# LED_Thermo.net
KiCad netlist of a schematic drawn in EAGLE
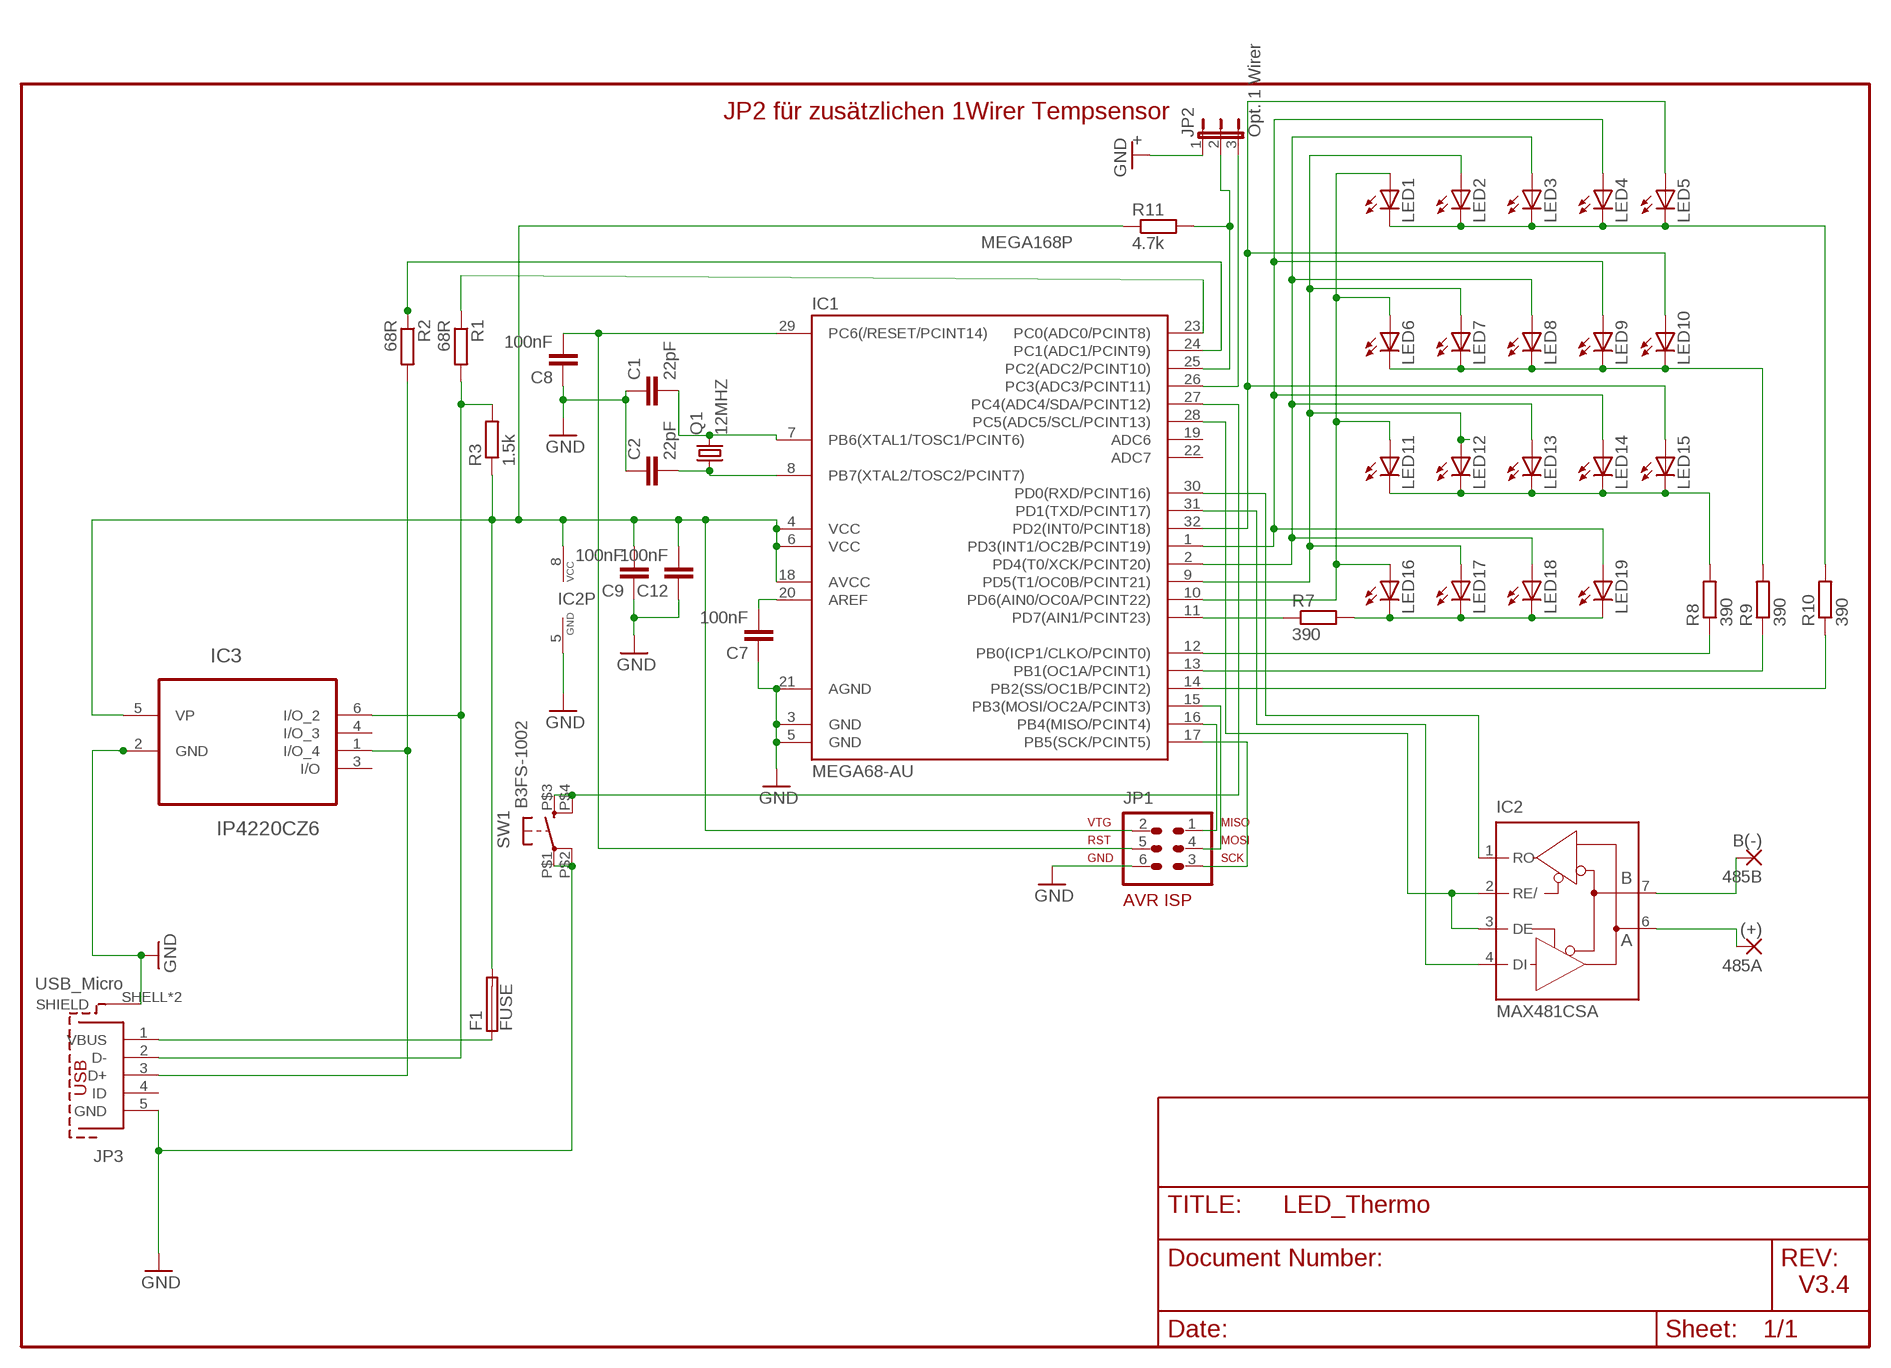
[diagram p0: schematic, sheet 1]

(export (version "E")
  (design (tool "Eeschema 10.0.6"))
  (components
    (comp (ref "485A")
      (value "(+)")
      (footprint "eagle-import:2,54_1,0")
      (libsource (lib "eagle-import") (part "2,54/1,0"))
    )
    (comp (ref "485B")
      (value "B(-)")
      (footprint "eagle-import:2,54_1,0")
      (libsource (lib "eagle-import") (part "2,54/1,0"))
    )
    (comp (ref "C1")
      (value "22pF")
      (footprint "eagle-import:C0805")
      (libsource (lib "eagle-import") (part "C-EUC0805"))
    )
    (comp (ref "C2")
      (value "22pF")
      (footprint "eagle-import:C0805")
      (libsource (lib "eagle-import") (part "C-EUC0805"))
    )
    (comp (ref "C7")
      (value "100nF")
      (footprint "eagle-import:C0805")
      (libsource (lib "eagle-import") (part "C-EUC0805"))
    )
    (comp (ref "C8")
      (value "100nF")
      (footprint "eagle-import:C0805")
      (libsource (lib "eagle-import") (part "C-EUC0805"))
    )
    (comp (ref "C9")
      (value "100nF")
      (footprint "eagle-import:C0805")
      (libsource (lib "eagle-import") (part "C-EUC0805"))
    )
    (comp (ref "C12")
      (value "100nF")
      (footprint "eagle-import:C0805")
      (libsource (lib "eagle-import") (part "C-EUC0805"))
    )
    (comp (ref "F1")
      (value "FUSE")
      (footprint "eagle-import:FUSE_1206")
      (libsource (lib "eagle-import") (part "FUSE"))
    )
    (comp (ref "IC1")
      (value "MEGA68-AU")
      (footprint "eagle-import:TQFP32-08")
      (libsource (lib "eagle-import") (part "MEGA48/88/168-AU"))
    )
    (comp (ref "IC2")
      (value "MAX481CSA")
      (footprint "eagle-import:SO08")
      (libsource (lib "eagle-import") (part "MAX481CSA"))
    )
    (comp (ref "IC3")
      (value "IP4220CZ6")
      (footprint "eagle-import:SOT95P275X110-6N")
      (fields (field (name "MF") "Nexperia USA"))
      (libsource (lib "eagle-import") (part "IP4220CZ6"))
    )
    (comp (ref "JP1")
      (value "AVR-ISP-6")
      (footprint "eagle-import:AVR-ISP-6")
      (libsource (lib "eagle-import") (part "AVR-ISP-6"))
    )
    (comp (ref "JP2")
      (value "Opt. 1 Wirer")
      (footprint "eagle-import:JP2")
      (libsource (lib "eagle-import") (part "JP2E"))
    )
    (comp (ref "JP3")
      (value "USB_Micro")
      (footprint "eagle-import:614105150721")
      (libsource (lib "eagle-import") (part "614105150721"))
    )
    (comp (ref "LED1")
      (value "LED3MM")
      (footprint "eagle-import:LED3MM")
      (libsource (lib "eagle-import") (part "LED3MM"))
    )
    (comp (ref "LED2")
      (value "LED3MM")
      (footprint "eagle-import:LED3MM")
      (libsource (lib "eagle-import") (part "LED3MM"))
    )
    (comp (ref "LED3")
      (value "LED3MM")
      (footprint "eagle-import:LED3MM")
      (libsource (lib "eagle-import") (part "LED3MM"))
    )
    (comp (ref "LED4")
      (value "LED3MM")
      (footprint "eagle-import:LED3MM")
      (libsource (lib "eagle-import") (part "LED3MM"))
    )
    (comp (ref "LED5")
      (value "LED3MM")
      (footprint "eagle-import:LED3MM")
      (libsource (lib "eagle-import") (part "LED3MM"))
    )
    (comp (ref "LED6")
      (value "LED3MM")
      (footprint "eagle-import:LED3MM")
      (libsource (lib "eagle-import") (part "LED3MM"))
    )
    (comp (ref "LED7")
      (value "LED3MM")
      (footprint "eagle-import:LED3MM")
      (libsource (lib "eagle-import") (part "LED3MM"))
    )
    (comp (ref "LED8")
      (value "LED3MM")
      (footprint "eagle-import:LED3MM")
      (libsource (lib "eagle-import") (part "LED3MM"))
    )
    (comp (ref "LED9")
      (value "LED3MM")
      (footprint "eagle-import:LED3MM")
      (libsource (lib "eagle-import") (part "LED3MM"))
    )
    (comp (ref "LED10")
      (value "LED3MM")
      (footprint "eagle-import:LED3MM")
      (libsource (lib "eagle-import") (part "LED3MM"))
    )
    (comp (ref "LED11")
      (value "LED3MM")
      (footprint "eagle-import:LED3MM")
      (libsource (lib "eagle-import") (part "LED3MM"))
    )
    (comp (ref "LED12")
      (value "LED3MM")
      (footprint "eagle-import:LED3MM")
      (libsource (lib "eagle-import") (part "LED3MM"))
    )
    (comp (ref "LED13")
      (value "LED3MM")
      (footprint "eagle-import:LED3MM")
      (libsource (lib "eagle-import") (part "LED3MM"))
    )
    (comp (ref "LED14")
      (value "LED3MM")
      (footprint "eagle-import:LED3MM")
      (libsource (lib "eagle-import") (part "LED3MM"))
    )
    (comp (ref "LED15")
      (value "LED3MM")
      (footprint "eagle-import:LED3MM")
      (libsource (lib "eagle-import") (part "LED3MM"))
    )
    (comp (ref "LED16")
      (value "LED3MM")
      (footprint "eagle-import:LED3MM")
      (libsource (lib "eagle-import") (part "LED3MM"))
    )
    (comp (ref "LED17")
      (value "LED3MM")
      (footprint "eagle-import:LED3MM")
      (libsource (lib "eagle-import") (part "LED3MM"))
    )
    (comp (ref "LED18")
      (value "LED3MM")
      (footprint "eagle-import:LED3MM")
      (libsource (lib "eagle-import") (part "LED3MM"))
    )
    (comp (ref "LED19")
      (value "LED3MM")
      (footprint "eagle-import:LED3MM")
      (libsource (lib "eagle-import") (part "LED3MM"))
    )
    (comp (ref "Q1")
      (value "12MHZ")
      (footprint "eagle-import:HC18U-V")
      (libsource (lib "eagle-import") (part "CRYSTALHC18U-V"))
    )
    (comp (ref "R1")
      (value "68R")
      (footprint "eagle-import:M0805")
      (libsource (lib "eagle-import") (part "R-EU_M0805"))
    )
    (comp (ref "R2")
      (value "68R")
      (footprint "eagle-import:M0805")
      (libsource (lib "eagle-import") (part "R-EU_M0805"))
    )
    (comp (ref "R3")
      (value "1.5k")
      (footprint "eagle-import:M0805")
      (libsource (lib "eagle-import") (part "R-EU_M0805"))
    )
    (comp (ref "R7")
      (value "390")
      (footprint "eagle-import:M0805")
      (libsource (lib "eagle-import") (part "R-EU_M0805"))
    )
    (comp (ref "R8")
      (value "390")
      (footprint "eagle-import:M0805")
      (libsource (lib "eagle-import") (part "R-EU_M0805"))
    )
    (comp (ref "R9")
      (value "390")
      (footprint "eagle-import:M0805")
      (libsource (lib "eagle-import") (part "R-EU_M0805"))
    )
    (comp (ref "R10")
      (value "390")
      (footprint "eagle-import:M0805")
      (libsource (lib "eagle-import") (part "R-EU_M0805"))
    )
    (comp (ref "R11")
      (value "4.7k")
      (footprint "eagle-import:M0805")
      (libsource (lib "eagle-import") (part "R-EU_M0805"))
    )
    (comp (ref "SW1")
      (value "B3FS-1002")
      (footprint "eagle-import:B3FS-1002")
      (libsource (lib "eagle-import") (part "B3FS-10XX"))
    )
  )
  (nets
    (net (code "1") (name "GND") (class "Default")
      (node (ref "C1") (pin "1") (pinfunction "1_1") (pintype "passive"))
      (node (ref "C12") (pin "1") (pinfunction "1_1") (pintype "passive"))
      (node (ref "C2") (pin "1") (pinfunction "1_1") (pintype "passive"))
      (node (ref "C7") (pin "1") (pinfunction "1_1") (pintype "passive"))
      (node (ref "C8") (pin "1") (pinfunction "1_1") (pintype "passive"))
      (node (ref "C9") (pin "1") (pinfunction "1_1") (pintype "passive"))
      (node (ref "IC1") (pin "21") (pinfunction "AGND_21") (pintype "power_in"))
      (node (ref "IC1") (pin "3") (pinfunction "GND_3") (pintype "power_in"))
      (node (ref "IC1") (pin "5") (pinfunction "GND_5") (pintype "power_in"))
      (node (ref "IC2") (pin "5") (pinfunction "GND_5") (pintype "power_in"))
      (node (ref "IC3") (pin "2") (pinfunction "GND_2") (pintype "passive"))
      (node (ref "JP1") (pin "6") (pinfunction "6_6") (pintype "passive"))
      (node (ref "JP2") (pin "1") (pinfunction "1_1") (pintype "passive"))
      (node (ref "JP3") (pin "5") (pinfunction "GND_5") (pintype "passive"))
      (node (ref "JP3") (pin "SHELL") (pinfunction "SHIELD_SHELL") (pintype "passive"))
      (node (ref "JP3") (pin "SHELL1") (pinfunction "SHIELD_SHELL1") (pintype "passive"))
      (node (ref "SW1") (pin "P$1") (pinfunction "P_P$1") (pintype "passive"))
      (node (ref "SW1") (pin "P$2") (pinfunction "P1_P$2") (pintype "passive"))
    )
    (net (code "2") (name "Net-(485A-P)") (class "Default")
      (node (ref "485A") (pin "1") (pinfunction "P_1") (pintype "passive"))
      (node (ref "IC2") (pin "6") (pinfunction "A_6") (pintype "passive"))
    )
    (net (code "3") (name "Net-(485B-P)") (class "Default")
      (node (ref "485B") (pin "1") (pinfunction "P_1") (pintype "passive"))
      (node (ref "IC2") (pin "7") (pinfunction "B_7") (pintype "passive"))
    )
    (net (code "4") (name "Net-(IC1-AREF)") (class "Default")
      (node (ref "C7") (pin "2") (pinfunction "2_2") (pintype "passive"))
      (node (ref "IC1") (pin "20") (pinfunction "AREF_20") (pintype "passive"))
    )
    (net (code "5") (name "Net-(IC1-AVCC)") (class "Default")
      (node (ref "C12") (pin "2") (pinfunction "2_2") (pintype "passive"))
      (node (ref "C9") (pin "2") (pinfunction "2_2") (pintype "passive"))
      (node (ref "F1") (pin "2") (pinfunction "2_2") (pintype "passive"))
      (node (ref "IC1") (pin "18") (pinfunction "AVCC_18") (pintype "passive"))
      (node (ref "IC1") (pin "4") (pinfunction "VCC_4") (pintype "power_in"))
      (node (ref "IC1") (pin "6") (pinfunction "VCC_6") (pintype "power_in"))
      (node (ref "IC2") (pin "8") (pinfunction "VCC_8") (pintype "power_in"))
      (node (ref "IC3") (pin "5") (pinfunction "VP_5") (pintype "power_in"))
      (node (ref "JP1") (pin "2") (pinfunction "2_2") (pintype "passive"))
      (node (ref "R11") (pin "1") (pinfunction "1_1") (pintype "passive"))
      (node (ref "R3") (pin "1") (pinfunction "1_1") (pintype "passive"))
    )
    (net (code "6") (name "Net-(IC1-PB0(ICP1{slash}CLKO{slash}PCINT0))") (class "Default")
      (node (ref "IC1") (pin "12") (pinfunction "PB0(ICP1/CLKO/PCINT0)_12") (pintype "bidirectional"))
      (node (ref "R8") (pin "1") (pinfunction "1_1") (pintype "passive"))
    )
    (net (code "7") (name "Net-(IC1-PB1(OC1A{slash}PCINT1))") (class "Default")
      (node (ref "IC1") (pin "13") (pinfunction "PB1(OC1A/PCINT1)_13") (pintype "bidirectional"))
      (node (ref "R9") (pin "1") (pinfunction "1_1") (pintype "passive"))
    )
    (net (code "8") (name "Net-(IC1-PB2(SS{slash}OC1B{slash}PCINT2))") (class "Default")
      (node (ref "IC1") (pin "14") (pinfunction "PB2(SS/OC1B/PCINT2)_14") (pintype "bidirectional"))
      (node (ref "R10") (pin "1") (pinfunction "1_1") (pintype "passive"))
    )
    (net (code "9") (name "Net-(IC1-PB3(MOSI{slash}OC2A{slash}PCINT3))") (class "Default")
      (node (ref "IC1") (pin "15") (pinfunction "PB3(MOSI/OC2A/PCINT3)_15") (pintype "bidirectional"))
      (node (ref "JP1") (pin "4") (pinfunction "4_4") (pintype "passive"))
    )
    (net (code "10") (name "Net-(IC1-PB4(MISO{slash}PCINT4))") (class "Default")
      (node (ref "IC1") (pin "16") (pinfunction "PB4(MISO/PCINT4)_16") (pintype "bidirectional"))
      (node (ref "JP1") (pin "1") (pinfunction "1_1") (pintype "passive"))
    )
    (net (code "11") (name "Net-(IC1-PB5(SCK{slash}PCINT5))") (class "Default")
      (node (ref "IC1") (pin "17") (pinfunction "PB5(SCK/PCINT5)_17") (pintype "bidirectional"))
      (node (ref "JP1") (pin "3") (pinfunction "3_3") (pintype "passive"))
    )
    (net (code "12") (name "Net-(IC1-PB6(XTAL1{slash}TOSC1{slash}PCINT6))") (class "Default")
      (node (ref "C1") (pin "2") (pinfunction "2_2") (pintype "passive"))
      (node (ref "IC1") (pin "7") (pinfunction "PB6(XTAL1/TOSC1/PCINT6)_7") (pintype "bidirectional"))
      (node (ref "Q1") (pin "2") (pinfunction "2_2") (pintype "passive"))
    )
    (net (code "13") (name "Net-(IC1-PB7(XTAL2{slash}TOSC2{slash}PCINT7))") (class "Default")
      (node (ref "C2") (pin "2") (pinfunction "2_2") (pintype "passive"))
      (node (ref "IC1") (pin "8") (pinfunction "PB7(XTAL2/TOSC2/PCINT7)_8") (pintype "bidirectional"))
      (node (ref "Q1") (pin "1") (pinfunction "1_1") (pintype "passive"))
    )
    (net (code "14") (name "Net-(IC1-PC0(ADC0{slash}PCINT8))") (class "Default")
      (node (ref "IC1") (pin "23") (pinfunction "PC0(ADC0/PCINT8)_23") (pintype "bidirectional"))
      (node (ref "R1") (pin "1") (pinfunction "1_1") (pintype "passive"))
    )
    (net (code "15") (name "Net-(IC1-PC1(ADC1{slash}PCINT9))") (class "Default")
      (node (ref "IC1") (pin "24") (pinfunction "PC1(ADC1/PCINT9)_24") (pintype "bidirectional"))
      (node (ref "R2") (pin "1") (pinfunction "1_1") (pintype "passive"))
    )
    (net (code "16") (name "Net-(IC1-PC2(ADC2{slash}PCINT10))") (class "Default")
      (node (ref "IC1") (pin "25") (pinfunction "PC2(ADC2/PCINT10)_25") (pintype "bidirectional"))
      (node (ref "JP2") (pin "2") (pinfunction "2_2") (pintype "passive"))
      (node (ref "R11") (pin "2") (pinfunction "2_2") (pintype "passive"))
    )
    (net (code "17") (name "Net-(IC1-PC3(ADC3{slash}PCINT11))") (class "Default")
      (node (ref "IC1") (pin "26") (pinfunction "PC3(ADC3/PCINT11)_26") (pintype "bidirectional"))
      (node (ref "JP2") (pin "3") (pinfunction "3_3") (pintype "passive"))
    )
    (net (code "18") (name "Net-(IC1-PC4(ADC4{slash}SDA{slash}PCINT12))") (class "Default")
      (node (ref "IC1") (pin "27") (pinfunction "PC4(ADC4/SDA/PCINT12)_27") (pintype "bidirectional"))
      (node (ref "SW1") (pin "P$3") (pinfunction "S_P$3") (pintype "passive"))
      (node (ref "SW1") (pin "P$4") (pinfunction "S1_P$4") (pintype "passive"))
    )
    (net (code "19") (name "Net-(IC1-PC5(ADC5{slash}SCL{slash}PCINT13))") (class "Default")
      (node (ref "IC1") (pin "28") (pinfunction "PC5(ADC5/SCL/PCINT13)_28") (pintype "bidirectional"))
      (node (ref "IC2") (pin "2") (pinfunction "RE/_2") (pintype "input"))
      (node (ref "IC2") (pin "3") (pinfunction "DE_3") (pintype "input"))
    )
    (net (code "20") (name "Net-(IC1-PC6({slash}RESET{slash}PCINT14))") (class "Default")
      (node (ref "C8") (pin "2") (pinfunction "2_2") (pintype "passive"))
      (node (ref "IC1") (pin "29") (pinfunction "PC6(/RESET/PCINT14)_29") (pintype "bidirectional"))
      (node (ref "JP1") (pin "5") (pinfunction "5_5") (pintype "passive"))
    )
    (net (code "21") (name "Net-(IC1-PD0(RXD{slash}PCINT16))") (class "Default")
      (node (ref "IC1") (pin "30") (pinfunction "PD0(RXD/PCINT16)_30") (pintype "bidirectional"))
      (node (ref "IC2") (pin "1") (pinfunction "RO_1") (pintype "output"))
    )
    (net (code "22") (name "Net-(IC1-PD1(TXD{slash}PCINT17))") (class "Default")
      (node (ref "IC1") (pin "31") (pinfunction "PD1(TXD/PCINT17)_31") (pintype "bidirectional"))
      (node (ref "IC2") (pin "4") (pinfunction "DI_4") (pintype "input"))
    )
    (net (code "23") (name "Net-(IC1-PD2(INT0{slash}PCINT18))") (class "Default")
      (node (ref "IC1") (pin "32") (pinfunction "PD2(INT0/PCINT18)_32") (pintype "bidirectional"))
      (node (ref "LED10") (pin "A") (pinfunction "A_A") (pintype "passive"))
      (node (ref "LED15") (pin "A") (pinfunction "A_A") (pintype "passive"))
      (node (ref "LED5") (pin "A") (pinfunction "A_A") (pintype "passive"))
    )
    (net (code "24") (name "Net-(IC1-PD3(INT1{slash}OC2B{slash}PCINT19))") (class "Default")
      (node (ref "IC1") (pin "1") (pinfunction "PD3(INT1/OC2B/PCINT19)_1") (pintype "bidirectional"))
      (node (ref "LED14") (pin "A") (pinfunction "A_A") (pintype "passive"))
      (node (ref "LED19") (pin "A") (pinfunction "A_A") (pintype "passive"))
      (node (ref "LED4") (pin "A") (pinfunction "A_A") (pintype "passive"))
      (node (ref "LED9") (pin "A") (pinfunction "A_A") (pintype "passive"))
    )
    (net (code "25") (name "Net-(IC1-PD4(T0{slash}XCK{slash}PCINT20))") (class "Default")
      (node (ref "IC1") (pin "2") (pinfunction "PD4(T0/XCK/PCINT20)_2") (pintype "bidirectional"))
      (node (ref "LED13") (pin "A") (pinfunction "A_A") (pintype "passive"))
      (node (ref "LED18") (pin "A") (pinfunction "A_A") (pintype "passive"))
      (node (ref "LED3") (pin "A") (pinfunction "A_A") (pintype "passive"))
      (node (ref "LED8") (pin "A") (pinfunction "A_A") (pintype "passive"))
    )
    (net (code "26") (name "Net-(IC1-PD5(T1{slash}OC0B{slash}PCINT21))") (class "Default")
      (node (ref "IC1") (pin "9") (pinfunction "PD5(T1/OC0B/PCINT21)_9") (pintype "bidirectional"))
      (node (ref "LED12") (pin "A") (pinfunction "A_A") (pintype "passive"))
      (node (ref "LED17") (pin "A") (pinfunction "A_A") (pintype "passive"))
      (node (ref "LED2") (pin "A") (pinfunction "A_A") (pintype "passive"))
      (node (ref "LED7") (pin "A") (pinfunction "A_A") (pintype "passive"))
    )
    (net (code "27") (name "Net-(IC1-PD6(AIN0{slash}OC0A{slash}PCINT22))") (class "Default")
      (node (ref "IC1") (pin "10") (pinfunction "PD6(AIN0/OC0A/PCINT22)_10") (pintype "bidirectional"))
      (node (ref "LED1") (pin "A") (pinfunction "A_A") (pintype "passive"))
      (node (ref "LED11") (pin "A") (pinfunction "A_A") (pintype "passive"))
      (node (ref "LED16") (pin "A") (pinfunction "A_A") (pintype "passive"))
      (node (ref "LED6") (pin "A") (pinfunction "A_A") (pintype "passive"))
    )
    (net (code "28") (name "Net-(IC1-PD7(AIN1{slash}PCINT23))") (class "Default")
      (node (ref "IC1") (pin "11") (pinfunction "PD7(AIN1/PCINT23)_11") (pintype "bidirectional"))
      (node (ref "R7") (pin "1") (pinfunction "1_1") (pintype "passive"))
    )
    (net (code "29") (name "Net-(IC3-I{slash}O_2)") (class "Default")
      (node (ref "IC3") (pin "6") (pinfunction "I/O_2_6") (pintype "bidirectional"))
      (node (ref "JP3") (pin "2") (pinfunction "D-_2") (pintype "passive"))
      (node (ref "R1") (pin "2") (pinfunction "2_2") (pintype "passive"))
      (node (ref "R3") (pin "2") (pinfunction "2_2") (pintype "passive"))
    )
    (net (code "30") (name "Net-(IC3-I{slash}O_4)") (class "Default")
      (node (ref "IC3") (pin "1") (pinfunction "I/O_4_1") (pintype "bidirectional"))
      (node (ref "JP3") (pin "3") (pinfunction "D+_3") (pintype "passive"))
      (node (ref "R2") (pin "2") (pinfunction "2_2") (pintype "passive"))
    )
    (net (code "31") (name "Net-(JP3-VBUS)") (class "Default")
      (node (ref "F1") (pin "1") (pinfunction "1_1") (pintype "passive"))
      (node (ref "JP3") (pin "1") (pinfunction "VBUS_1") (pintype "passive"))
    )
    (net (code "32") (name "Net-(LED1-C)") (class "Default")
      (node (ref "LED1") (pin "K") (pinfunction "C_K") (pintype "passive"))
      (node (ref "LED2") (pin "K") (pinfunction "C_K") (pintype "passive"))
      (node (ref "LED3") (pin "K") (pinfunction "C_K") (pintype "passive"))
      (node (ref "LED4") (pin "K") (pinfunction "C_K") (pintype "passive"))
      (node (ref "LED5") (pin "K") (pinfunction "C_K") (pintype "passive"))
      (node (ref "R10") (pin "2") (pinfunction "2_2") (pintype "passive"))
    )
    (net (code "33") (name "Net-(LED10-C)") (class "Default")
      (node (ref "LED10") (pin "K") (pinfunction "C_K") (pintype "passive"))
      (node (ref "LED6") (pin "K") (pinfunction "C_K") (pintype "passive"))
      (node (ref "LED7") (pin "K") (pinfunction "C_K") (pintype "passive"))
      (node (ref "LED8") (pin "K") (pinfunction "C_K") (pintype "passive"))
      (node (ref "LED9") (pin "K") (pinfunction "C_K") (pintype "passive"))
      (node (ref "R9") (pin "2") (pinfunction "2_2") (pintype "passive"))
    )
    (net (code "34") (name "Net-(LED11-C)") (class "Default")
      (node (ref "LED11") (pin "K") (pinfunction "C_K") (pintype "passive"))
      (node (ref "LED12") (pin "K") (pinfunction "C_K") (pintype "passive"))
      (node (ref "LED13") (pin "K") (pinfunction "C_K") (pintype "passive"))
      (node (ref "LED14") (pin "K") (pinfunction "C_K") (pintype "passive"))
      (node (ref "LED15") (pin "K") (pinfunction "C_K") (pintype "passive"))
      (node (ref "R8") (pin "2") (pinfunction "2_2") (pintype "passive"))
    )
    (net (code "35") (name "Net-(LED16-C)") (class "Default")
      (node (ref "LED16") (pin "K") (pinfunction "C_K") (pintype "passive"))
      (node (ref "LED17") (pin "K") (pinfunction "C_K") (pintype "passive"))
      (node (ref "LED18") (pin "K") (pinfunction "C_K") (pintype "passive"))
      (node (ref "LED19") (pin "K") (pinfunction "C_K") (pintype "passive"))
      (node (ref "R7") (pin "2") (pinfunction "2_2") (pintype "passive"))
    )
    (net (code "36") (name "unconnected-(IC1-ADC6-Pad19)") (class "Default")
      (node (ref "IC1") (pin "19") (pinfunction "ADC6_19") (pintype "passive"))
    )
    (net (code "37") (name "unconnected-(IC1-ADC7-Pad22)") (class "Default")
      (node (ref "IC1") (pin "22") (pinfunction "ADC7_22") (pintype "passive"))
    )
    (net (code "38") (name "unconnected-(IC3-I{slash}O-Pad3)") (class "Default")
      (node (ref "IC3") (pin "3") (pinfunction "I/O_3") (pintype "bidirectional"))
    )
    (net (code "39") (name "unconnected-(IC3-I{slash}O_3-Pad4)") (class "Default")
      (node (ref "IC3") (pin "4") (pinfunction "I/O_3_4") (pintype "bidirectional"))
    )
    (net (code "40") (name "unconnected-(JP3-ID-Pad4)") (class "Default")
      (node (ref "JP3") (pin "4") (pinfunction "ID_4") (pintype "passive"))
    )
  )
)
